# Channel.net
KiCad netlist of a schematic drawn in Altium Designer
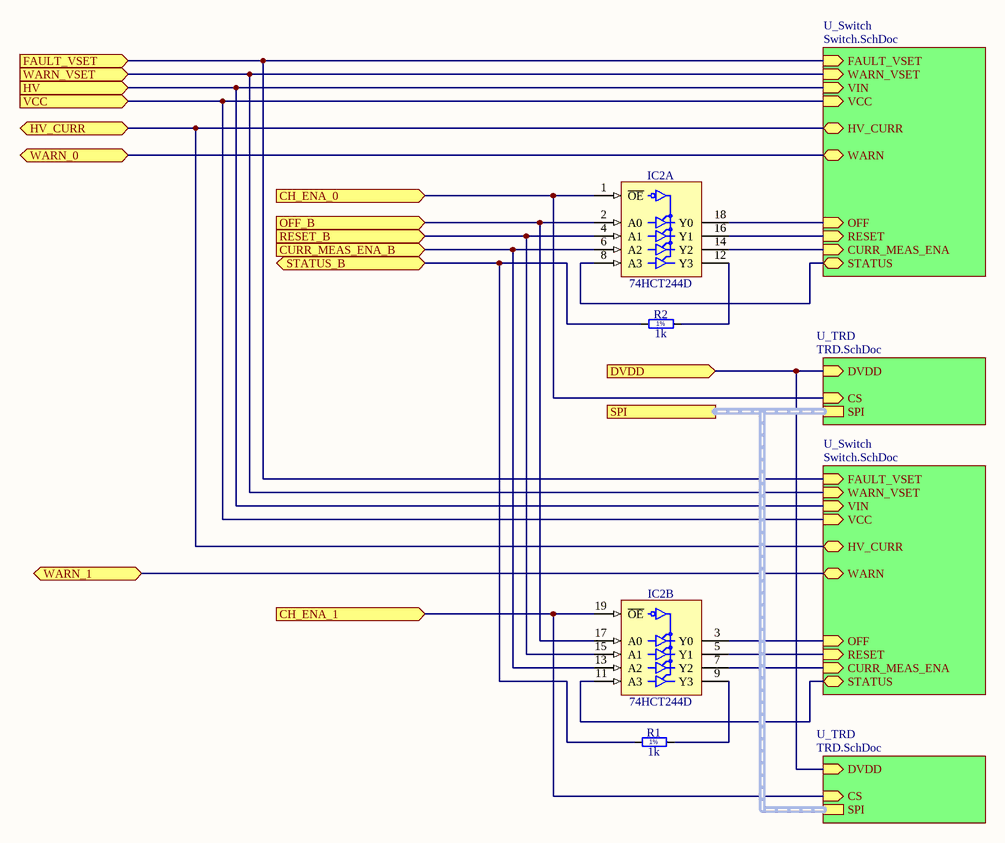
[diagram p0: Channel.SchDoc]

(export (version "E")
  (design (tool "Eeschema 10.0.6"))
  (components
    (comp (ref "IC2")
      (value "74HCT244D")
      (footprint "SOIC127P1032X265-20N")
      (description "Octal Buffer And Line Driver with 3-State Ouputs")
      (fields (field (name "MANUFACTURER") "NXP SEMICONDUCTORS") (field (name "AUTHOR") "CERN DEM JLC"))
      (libsource (lib "ICs And Semiconductors") (part "74244"))
    )
    (comp (ref "R1")
      (value "1k")
      (footprint "RESC2012X60N")
      (description "Resistor - 1%")
      (fields
        (field (name "PART NUMBER") "R0805_1K_1%_0.33W_100PPM_VISHAY_CRCW-HP")
        (field (name "POWER") "0.33W")
        (field (name "AUTHOR") "CERN DEM JLC")
      )
      (libsource (lib "Resistors") (part "Resistor - 1%"))
    )
    (comp (ref "R2")
      (value "1k")
      (footprint "RESC2012X60N")
      (description "Resistor - 1%")
      (fields
        (field (name "PART NUMBER") "R0805_1K_1%_0.33W_100PPM_VISHAY_CRCW-HP")
        (field (name "POWER") "0.33W")
        (field (name "AUTHOR") "CERN DEM JLC")
      )
      (libsource (lib "Resistors") (part "Resistor - 1%"))
    )
  )
  (nets
    (net (code "2") (name "/CH_ENA_0") (class "Default")
      (node (ref "IC2") (pin "1") (pinfunction "~{OE}_1") (pintype "input"))
    )
    (net (code "3") (name "/CH_ENA_1") (class "Default")
      (node (ref "IC2") (pin "19") (pinfunction "~{OE}_19") (pintype "input"))
    )
    (net (code "4") (name "/CURR_MEAS_ENA") (class "Default")
      (node (ref "IC2") (pin "7") (pinfunction "Y2_7") (pintype "tri_state"))
    )
    (net (code "5") (name "/CURR_MEAS_ENA_1") (class "Default")
      (node (ref "IC2") (pin "14") (pinfunction "Y2_14") (pintype "tri_state"))
    )
    (net (code "6") (name "/CURR_MEAS_ENA_B") (class "Default")
      (node (ref "IC2") (pin "13") (pinfunction "A2_13") (pintype "input"))
      (node (ref "IC2") (pin "6") (pinfunction "A2_6") (pintype "input"))
    )
    (net (code "11") (name "/OFF") (class "Default")
      (node (ref "IC2") (pin "3") (pinfunction "Y0_3") (pintype "tri_state"))
    )
    (net (code "12") (name "/OFF_1") (class "Default")
      (node (ref "IC2") (pin "18") (pinfunction "Y0_18") (pintype "tri_state"))
    )
    (net (code "13") (name "/OFF_B") (class "Default")
      (node (ref "IC2") (pin "17") (pinfunction "A0_17") (pintype "input"))
      (node (ref "IC2") (pin "2") (pinfunction "A0_2") (pintype "input"))
    )
    (net (code "14") (name "/RESET") (class "Default")
      (node (ref "IC2") (pin "5") (pinfunction "Y1_5") (pintype "tri_state"))
    )
    (net (code "15") (name "/RESET_1") (class "Default")
      (node (ref "IC2") (pin "16") (pinfunction "Y1_16") (pintype "tri_state"))
    )
    (net (code "16") (name "/RESET_B") (class "Default")
      (node (ref "IC2") (pin "15") (pinfunction "A1_15") (pintype "input"))
      (node (ref "IC2") (pin "4") (pinfunction "A1_4") (pintype "input"))
    )
    (net (code "18") (name "/STATUS") (class "Default")
      (node (ref "IC2") (pin "11") (pinfunction "A3_11") (pintype "input"))
    )
    (net (code "19") (name "/STATUS_1") (class "Default")
      (node (ref "IC2") (pin "8") (pinfunction "A3_8") (pintype "input"))
    )
    (net (code "20") (name "/STATUS_B") (class "Default")
      (node (ref "R1") (pin "1") (pinfunction "1_1") (pintype "passive"))
      (node (ref "R2") (pin "1") (pinfunction "1_1") (pintype "passive"))
    )
    (net (code "24") (name "GND") (class "Default")
      (node (ref "IC2") (pin "10") (pinfunction "GND_10") (pintype "power_in"))
    )
    (net (code "25") (name "Net-(IC2A-Y3)") (class "Default")
      (node (ref "IC2") (pin "12") (pinfunction "Y3_12") (pintype "tri_state"))
      (node (ref "R2") (pin "2") (pinfunction "2_2") (pintype "passive"))
    )
    (net (code "26") (name "Net-(IC2B-Y3)") (class "Default")
      (node (ref "IC2") (pin "9") (pinfunction "Y3_9") (pintype "tri_state"))
      (node (ref "R1") (pin "2") (pinfunction "2_2") (pintype "passive"))
    )
    (net (code "27") (name "VCC") (class "Default")
      (node (ref "IC2") (pin "20") (pinfunction "VCC_20") (pintype "power_in"))
    )
  )
)
